# expenasion_board_template.net
KiCad netlist of a schematic drawn in EAGLE
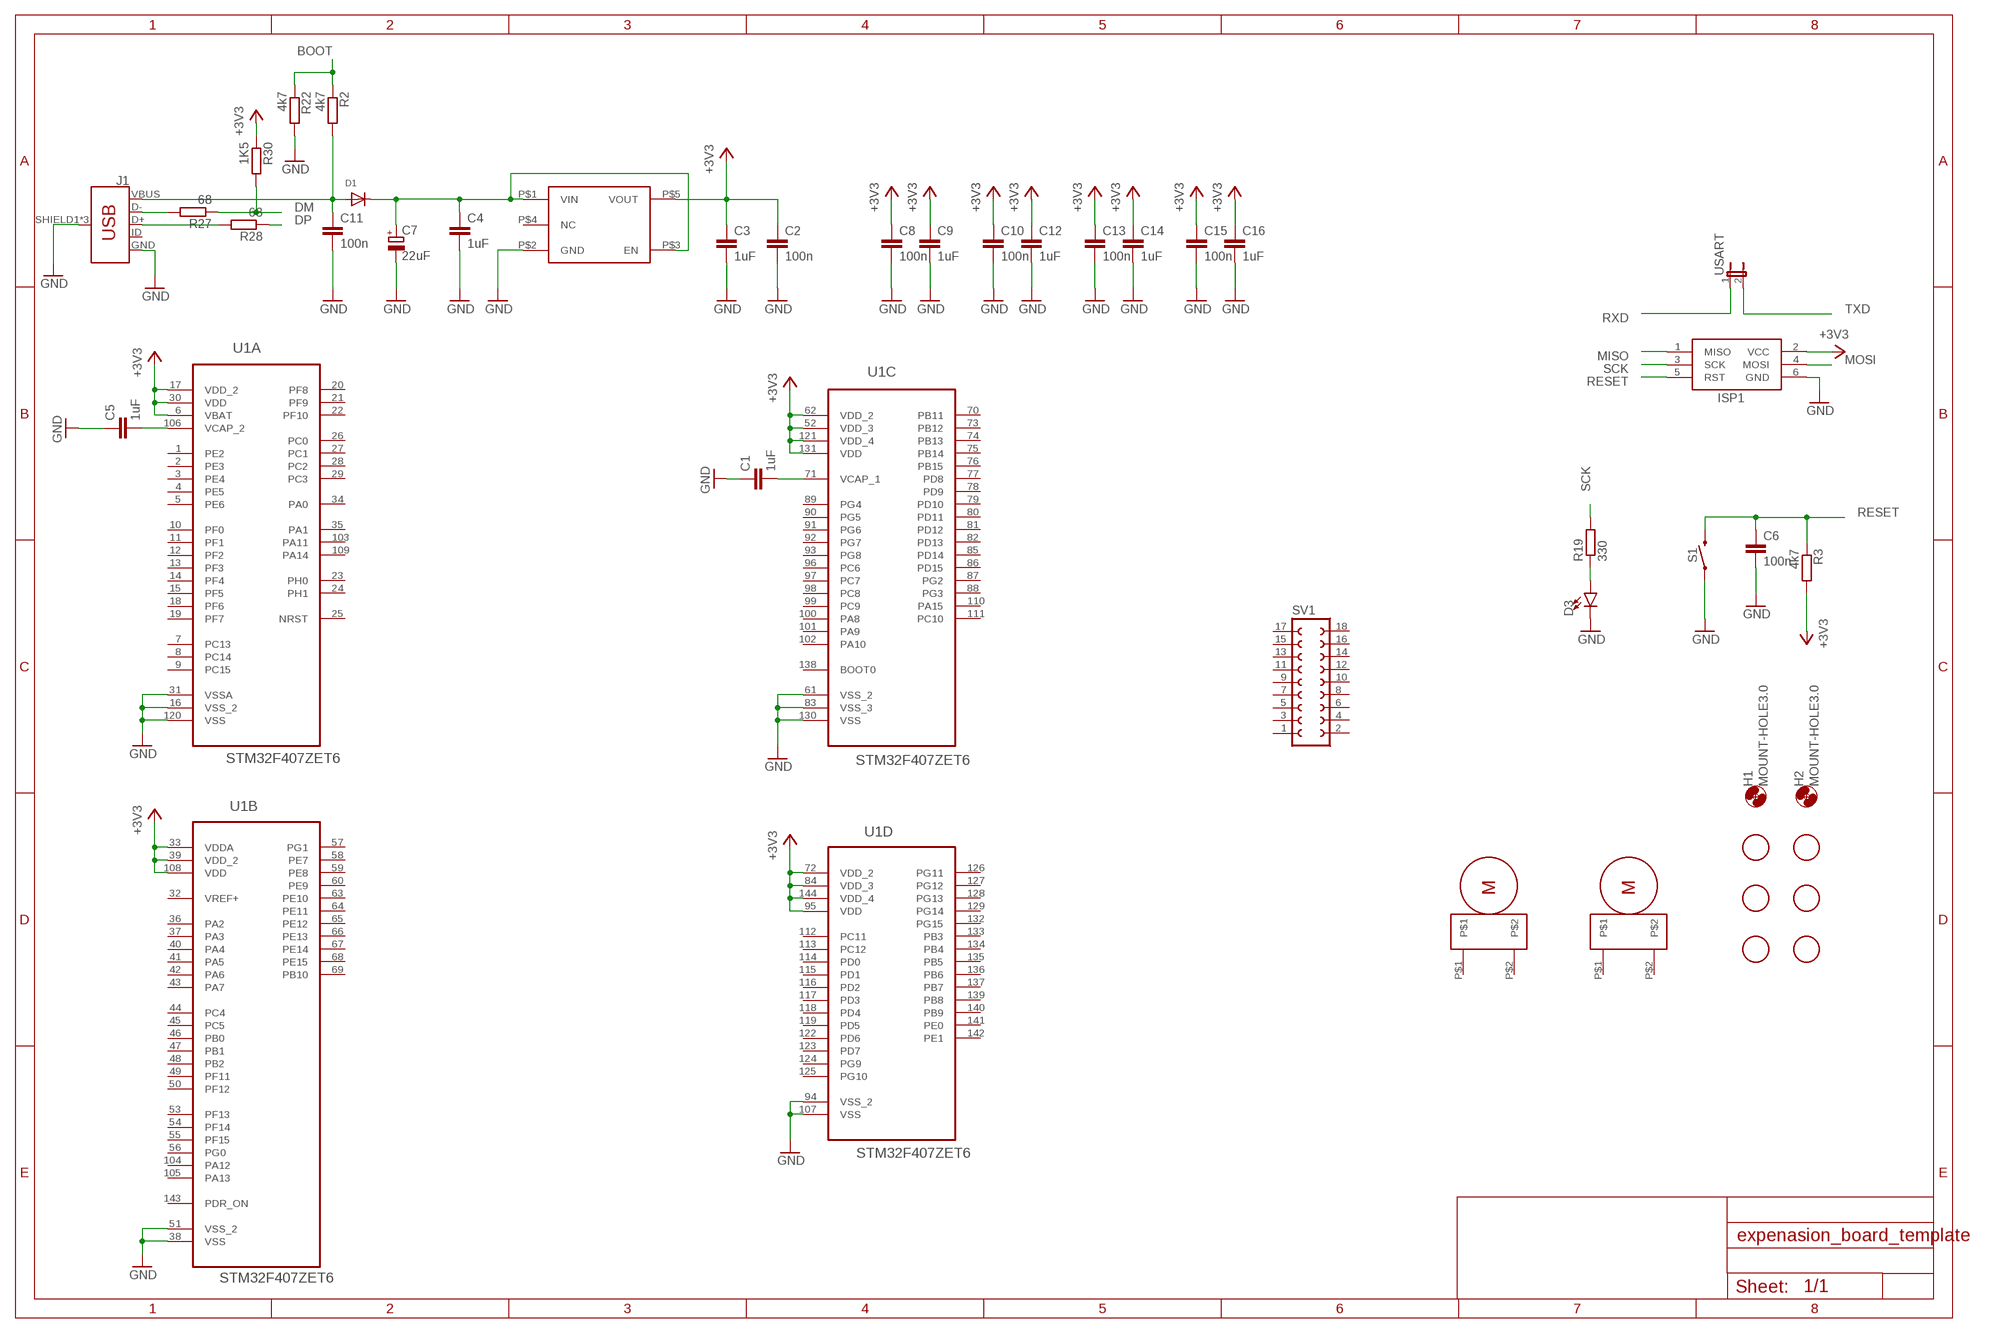
[diagram p0: schematic, sheet 1]

(export (version "E")
  (design (tool "Eeschema 10.0.6"))
  (components
    (comp (ref "C1")
      (value "1uF")
      (footprint "eagle-import:C0805")
      (libsource (lib "eagle-import") (part "C-EUC0805"))
    )
    (comp (ref "C2")
      (value "100n")
      (footprint "eagle-import:C0603")
      (libsource (lib "eagle-import") (part "C-EUC0603"))
    )
    (comp (ref "C3")
      (value "1uF")
      (footprint "eagle-import:C0805")
      (libsource (lib "eagle-import") (part "C-EUC0805"))
    )
    (comp (ref "C4")
      (value "1uF")
      (footprint "eagle-import:C0805")
      (libsource (lib "eagle-import") (part "C-EUC0805"))
    )
    (comp (ref "C5")
      (value "1uF")
      (footprint "eagle-import:C0805")
      (libsource (lib "eagle-import") (part "C-EUC0805"))
    )
    (comp (ref "C6")
      (value "100n")
      (footprint "eagle-import:C0603")
      (libsource (lib "eagle-import") (part "C-EUC0603"))
    )
    (comp (ref "C7")
      (value "22uF")
      (footprint "eagle-import:153CLV-0505")
      (libsource (lib "eagle-import") (part "CPOL-EU153CLV-0505"))
    )
    (comp (ref "C8")
      (value "100n")
      (footprint "eagle-import:C0603")
      (libsource (lib "eagle-import") (part "C-EUC0603"))
    )
    (comp (ref "C9")
      (value "1uF")
      (footprint "eagle-import:C0805")
      (libsource (lib "eagle-import") (part "C-EUC0805"))
    )
    (comp (ref "C10")
      (value "100n")
      (footprint "eagle-import:C0603")
      (libsource (lib "eagle-import") (part "C-EUC0603"))
    )
    (comp (ref "C11")
      (value "100n")
      (footprint "eagle-import:C0603")
      (libsource (lib "eagle-import") (part "C-EUC0603"))
    )
    (comp (ref "C12")
      (value "1uF")
      (footprint "eagle-import:C0805")
      (libsource (lib "eagle-import") (part "C-EUC0805"))
    )
    (comp (ref "C13")
      (value "100n")
      (footprint "eagle-import:C0603")
      (libsource (lib "eagle-import") (part "C-EUC0603"))
    )
    (comp (ref "C14")
      (value "1uF")
      (footprint "eagle-import:C0805")
      (libsource (lib "eagle-import") (part "C-EUC0805"))
    )
    (comp (ref "C15")
      (value "100n")
      (footprint "eagle-import:C0603")
      (libsource (lib "eagle-import") (part "C-EUC0603"))
    )
    (comp (ref "C16")
      (value "1uF")
      (footprint "eagle-import:C0805")
      (libsource (lib "eagle-import") (part "C-EUC0805"))
    )
    (comp (ref "D1")
      (value "DIODE_SOD-123FL")
      (footprint "eagle-import:SOD-123FL")
      (libsource (lib "eagle-import") (part "DIODE_SOD-123FL"))
    )
    (comp (ref "D3")
      (value "LED-FKIT-1206")
      (footprint "eagle-import:FKIT-LED-1206")
      (libsource (lib "eagle-import") (part "LED-FKIT-1206"))
    )
    (comp (ref "H1")
      (value "MOUNT-HOLE3.0")
      (footprint "eagle-import:3,0")
      (libsource (lib "eagle-import") (part "MOUNT-HOLE3.0"))
    )
    (comp (ref "H2")
      (value "MOUNT-HOLE3.0")
      (footprint "eagle-import:3,0")
      (libsource (lib "eagle-import") (part "MOUNT-HOLE3.0"))
    )
    (comp (ref "ISP1")
      (value "AVRISP-6")
      (footprint "eagle-import:AVRISP")
      (libsource (lib "eagle-import") (part "AVRISP-6"))
    )
    (comp (ref "J1")
      (value "USB_MICRO-B_FEMALE-SMT")
      (footprint "eagle-import:USB-B-MICRO-SMD")
      (libsource (lib "eagle-import") (part "USB_MICRO-B_FEMALE-SMT"))
    )
    (comp (ref "R2")
      (value "4k7")
      (footprint "eagle-import:R0603")
      (libsource (lib "eagle-import") (part "R-EU_R0603"))
    )
    (comp (ref "R3")
      (value "4k7")
      (footprint "eagle-import:R0603")
      (libsource (lib "eagle-import") (part "R-EU_R0603"))
    )
    (comp (ref "R19")
      (value "330")
      (footprint "eagle-import:R0603")
      (libsource (lib "eagle-import") (part "R-EU_R0603"))
    )
    (comp (ref "R22")
      (value "4k7")
      (footprint "eagle-import:R0603")
      (libsource (lib "eagle-import") (part "R-EU_R0603"))
    )
    (comp (ref "R27")
      (value "68")
      (footprint "eagle-import:R0603")
      (libsource (lib "eagle-import") (part "R-EU_R0603"))
    )
    (comp (ref "R28")
      (value "68")
      (footprint "eagle-import:R0603")
      (libsource (lib "eagle-import") (part "R-EU_R0603"))
    )
    (comp (ref "R30")
      (value "1K5")
      (footprint "eagle-import:R0603")
      (libsource (lib "eagle-import") (part "R-EU_R0603"))
    )
    (comp (ref "S1")
      (value "MOMENTARY-SWITCH-SPST-SMD-6.2MM-TALL")
      (footprint "eagle-import:TACTILE_SWITCH_SMD_6.2MM_TALL")
      (libsource (lib "eagle-import") (part "MOMENTARY-SWITCH-SPST-SMD-6.2MM-TALL"))
    )
    (comp (ref "SV1")
      (value "FE09-2")
      (footprint "eagle-import:FE09-2")
      (libsource (lib "eagle-import") (part "FE09-2"))
    )
    (comp (ref "U$1")
      (value "FIDUCIAL")
      (footprint "eagle-import:FIDUCIAL_1MM")
      (libsource (lib "eagle-import") (part "FIDUCIAL"))
    )
    (comp (ref "U$2")
      (value "PLANETARY_GEAR_MOTOR")
      (footprint "eagle-import:PLANETARY_GEAR_MOTOR")
      (libsource (lib "eagle-import") (part "PLANETARY_GEAR_MOTOR"))
    )
    (comp (ref "U$3")
      (value "FIDUCIAL")
      (footprint "eagle-import:FIDUCIAL_1MM")
      (libsource (lib "eagle-import") (part "FIDUCIAL"))
    )
    (comp (ref "U$4")
      (value "FIDUCIAL")
      (footprint "eagle-import:FIDUCIAL_1MM")
      (libsource (lib "eagle-import") (part "FIDUCIAL"))
    )
    (comp (ref "U$5")
      (value "FIDUCIAL")
      (footprint "eagle-import:FIDUCIAL_1MM")
      (libsource (lib "eagle-import") (part "FIDUCIAL"))
    )
    (comp (ref "U$6")
      (value "FIDUCIAL")
      (footprint "eagle-import:FIDUCIAL_1MM")
      (libsource (lib "eagle-import") (part "FIDUCIAL"))
    )
    (comp (ref "U$7")
      (value "FIDUCIAL")
      (footprint "eagle-import:FIDUCIAL_1MM")
      (libsource (lib "eagle-import") (part "FIDUCIAL"))
    )
    (comp (ref "U$10")
      (value "PLANETARY_GEAR_MOTOR")
      (footprint "eagle-import:PLANETARY_GEAR_MOTOR")
      (libsource (lib "eagle-import") (part "PLANETARY_GEAR_MOTOR"))
    )
    (comp (ref "U$11")
      (value "MIC5504-3.3Y")
      (footprint "eagle-import:SOT23-5")
      (libsource (lib "eagle-import") (part "MIC5504-3.3Y"))
    )
    (comp (ref "U1")
      (value "STM32F407ZET6")
      (footprint "eagle-import:QFP50P2000X2000X160-144N")
      (libsource (lib "eagle-import") (part "STM32F407ZET6"))
    )
    (comp (ref "USART")
      (value "JP1E")
      (footprint "eagle-import:JP1")
      (libsource (lib "eagle-import") (part "JP1E"))
    )
  )
  (nets
    (net (code "1") (name "+3V3") (class "Default")
      (node (ref "C10") (pin "1") (pinfunction "1_1") (pintype "passive"))
      (node (ref "C12") (pin "1") (pinfunction "1_1") (pintype "passive"))
      (node (ref "C13") (pin "1") (pinfunction "1_1") (pintype "passive"))
      (node (ref "C14") (pin "1") (pinfunction "1_1") (pintype "passive"))
      (node (ref "C15") (pin "1") (pinfunction "1_1") (pintype "passive"))
      (node (ref "C16") (pin "1") (pinfunction "1_1") (pintype "passive"))
      (node (ref "C2") (pin "1") (pinfunction "1_1") (pintype "passive"))
      (node (ref "C3") (pin "1") (pinfunction "1_1") (pintype "passive"))
      (node (ref "C8") (pin "1") (pinfunction "1_1") (pintype "passive"))
      (node (ref "C9") (pin "1") (pinfunction "1_1") (pintype "passive"))
      (node (ref "ISP1") (pin "2") (pinfunction "VCC_2") (pintype "power_in"))
      (node (ref "R3") (pin "2") (pinfunction "2_2") (pintype "passive"))
      (node (ref "R30") (pin "1") (pinfunction "1_1") (pintype "passive"))
      (node (ref "U$11") (pin "P$5") (pinfunction "VOUT_P$5") (pintype "bidirectional"))
      (node (ref "U1") (pin "108") (pinfunction "VDD_108") (pintype "power_in"))
      (node (ref "U1") (pin "121") (pinfunction "VDD_4_121") (pintype "power_in"))
      (node (ref "U1") (pin "131") (pinfunction "VDD_131") (pintype "power_in"))
      (node (ref "U1") (pin "144") (pinfunction "VDD_4_144") (pintype "power_in"))
      (node (ref "U1") (pin "17") (pinfunction "VDD_2_17") (pintype "power_in"))
      (node (ref "U1") (pin "30") (pinfunction "VDD_30") (pintype "power_in"))
      (node (ref "U1") (pin "33") (pinfunction "VDDA_33") (pintype "power_in"))
      (node (ref "U1") (pin "39") (pinfunction "VDD_2_39") (pintype "power_in"))
      (node (ref "U1") (pin "52") (pinfunction "VDD_3_52") (pintype "power_in"))
      (node (ref "U1") (pin "6") (pinfunction "VBAT_6") (pintype "power_in"))
      (node (ref "U1") (pin "62") (pinfunction "VDD_2_62") (pintype "power_in"))
      (node (ref "U1") (pin "72") (pinfunction "VDD_2_72") (pintype "power_in"))
      (node (ref "U1") (pin "84") (pinfunction "VDD_3_84") (pintype "power_in"))
      (node (ref "U1") (pin "95") (pinfunction "VDD_95") (pintype "power_in"))
    )
    (net (code "2") (name "/BOOT") (class "Default")
      (node (ref "R2") (pin "1") (pinfunction "1_1") (pintype "passive"))
      (node (ref "R22") (pin "1") (pinfunction "1_1") (pintype "passive"))
    )
    (net (code "3") (name "/DM") (class "Default")
      (node (ref "R27") (pin "1") (pinfunction "1_1") (pintype "passive"))
      (node (ref "R30") (pin "2") (pinfunction "2_2") (pintype "passive"))
    )
    (net (code "4") (name "/DP") (class "Default")
      (node (ref "R28") (pin "1") (pinfunction "1_1") (pintype "passive"))
    )
    (net (code "5") (name "/MISO") (class "Default")
      (node (ref "ISP1") (pin "1") (pinfunction "MISO_1") (pintype "input"))
    )
    (net (code "6") (name "/MOSI") (class "Default")
      (node (ref "ISP1") (pin "4") (pinfunction "MOSI_4") (pintype "output"))
    )
    (net (code "7") (name "/RESET") (class "Default")
      (node (ref "C6") (pin "1") (pinfunction "1_1") (pintype "passive"))
      (node (ref "ISP1") (pin "5") (pinfunction "RST_5") (pintype "output"))
      (node (ref "R3") (pin "1") (pinfunction "1_1") (pintype "passive"))
      (node (ref "S1") (pin "B2") (pinfunction "2_B2") (pintype "passive"))
    )
    (net (code "8") (name "/RXD") (class "Default")
      (node (ref "USART") (pin "1") (pinfunction "1_1") (pintype "passive"))
    )
    (net (code "9") (name "/SCK") (class "Default")
      (node (ref "ISP1") (pin "3") (pinfunction "SCK_3") (pintype "output"))
      (node (ref "R19") (pin "2") (pinfunction "2_2") (pintype "passive"))
    )
    (net (code "10") (name "/TXD") (class "Default")
      (node (ref "USART") (pin "2") (pinfunction "2_2") (pintype "passive"))
    )
    (net (code "11") (name "/VREF+") (class "Default")
      (node (ref "U1") (pin "32") (pinfunction "VREF+_32") (pintype "power_in"))
    )
    (net (code "12") (name "GND") (class "Default")
      (node (ref "C1") (pin "1") (pinfunction "1_1") (pintype "passive"))
      (node (ref "C10") (pin "2") (pinfunction "2_2") (pintype "passive"))
      (node (ref "C11") (pin "2") (pinfunction "2_2") (pintype "passive"))
      (node (ref "C12") (pin "2") (pinfunction "2_2") (pintype "passive"))
      (node (ref "C13") (pin "2") (pinfunction "2_2") (pintype "passive"))
      (node (ref "C14") (pin "2") (pinfunction "2_2") (pintype "passive"))
      (node (ref "C15") (pin "2") (pinfunction "2_2") (pintype "passive"))
      (node (ref "C16") (pin "2") (pinfunction "2_2") (pintype "passive"))
      (node (ref "C2") (pin "2") (pinfunction "2_2") (pintype "passive"))
      (node (ref "C3") (pin "2") (pinfunction "2_2") (pintype "passive"))
      (node (ref "C4") (pin "2") (pinfunction "2_2") (pintype "passive"))
      (node (ref "C5") (pin "1") (pinfunction "1_1") (pintype "passive"))
      (node (ref "C6") (pin "2") (pinfunction "2_2") (pintype "passive"))
      (node (ref "C7") (pin "-") (pinfunction "-_-") (pintype "passive"))
      (node (ref "C8") (pin "2") (pinfunction "2_2") (pintype "passive"))
      (node (ref "C9") (pin "2") (pinfunction "2_2") (pintype "passive"))
      (node (ref "D3") (pin "C") (pinfunction "C_C") (pintype "passive"))
      (node (ref "ISP1") (pin "6") (pinfunction "GND_6") (pintype "power_in"))
      (node (ref "J1") (pin "GND") (pinfunction "GND_GND") (pintype "power_in"))
      (node (ref "J1") (pin "SHIELD1") (pinfunction "SHIELD_SHIELD1") (pintype "bidirectional"))
      (node (ref "J1") (pin "SHIELD2") (pinfunction "SHIELD_SHIELD2") (pintype "bidirectional"))
      (node (ref "J1") (pin "SHIELD3") (pinfunction "SHIELD_SHIELD3") (pintype "bidirectional"))
      (node (ref "R22") (pin "2") (pinfunction "2_2") (pintype "passive"))
      (node (ref "S1") (pin "A2") (pinfunction "1_A2") (pintype "passive"))
      (node (ref "U$11") (pin "P$2") (pinfunction "GND_P$2") (pintype "bidirectional"))
      (node (ref "U1") (pin "107") (pinfunction "VSS_107") (pintype "passive"))
      (node (ref "U1") (pin "120") (pinfunction "VSS_120") (pintype "passive"))
      (node (ref "U1") (pin "130") (pinfunction "VSS_130") (pintype "passive"))
      (node (ref "U1") (pin "16") (pinfunction "VSS_2_16") (pintype "passive"))
      (node (ref "U1") (pin "31") (pinfunction "VSSA_31") (pintype "passive"))
      (node (ref "U1") (pin "38") (pinfunction "VSS_38") (pintype "passive"))
      (node (ref "U1") (pin "51") (pinfunction "VSS_2_51") (pintype "passive"))
      (node (ref "U1") (pin "61") (pinfunction "VSS_2_61") (pintype "passive"))
      (node (ref "U1") (pin "83") (pinfunction "VSS_3_83") (pintype "passive"))
      (node (ref "U1") (pin "94") (pinfunction "VSS_2_94") (pintype "passive"))
    )
    (net (code "13") (name "Net-(C11-Pad1)") (class "Default")
      (node (ref "C11") (pin "1") (pinfunction "1_1") (pintype "passive"))
      (node (ref "D1") (pin "A") (pinfunction "A_A") (pintype "passive"))
      (node (ref "J1") (pin "VBUS") (pinfunction "VBUS_VBUS") (pintype "power_in"))
      (node (ref "R2") (pin "2") (pinfunction "2_2") (pintype "passive"))
    )
    (net (code "14") (name "Net-(D3-PadA)") (class "Default")
      (node (ref "D3") (pin "A") (pinfunction "A_A") (pintype "passive"))
      (node (ref "R19") (pin "1") (pinfunction "1_1") (pintype "passive"))
    )
    (net (code "15") (name "Net-(J1-PadD+)") (class "Default")
      (node (ref "J1") (pin "D+") (pinfunction "D+_D+") (pintype "bidirectional"))
      (node (ref "R28") (pin "2") (pinfunction "2_2") (pintype "passive"))
    )
    (net (code "16") (name "Net-(J1-PadD-)") (class "Default")
      (node (ref "J1") (pin "D-") (pinfunction "D-_D-") (pintype "bidirectional"))
      (node (ref "R27") (pin "2") (pinfunction "2_2") (pintype "passive"))
    )
    (net (code "17") (name "Net-(U$11-EN)") (class "Default")
      (node (ref "C4") (pin "1") (pinfunction "1_1") (pintype "passive"))
      (node (ref "C7") (pin "+") (pinfunction "+_+") (pintype "passive"))
      (node (ref "D1") (pin "C") (pinfunction "C_C") (pintype "passive"))
      (node (ref "U$11") (pin "P$1") (pinfunction "VIN_P$1") (pintype "bidirectional"))
      (node (ref "U$11") (pin "P$3") (pinfunction "EN_P$3") (pintype "bidirectional"))
    )
    (net (code "18") (name "Net-(U1A-VCAP_2)") (class "Default")
      (node (ref "C5") (pin "2") (pinfunction "2_2") (pintype "passive"))
      (node (ref "U1") (pin "106") (pinfunction "VCAP_2_106") (pintype "power_in"))
    )
    (net (code "19") (name "Net-(U1C-VCAP_1)") (class "Default")
      (node (ref "C1") (pin "2") (pinfunction "2_2") (pintype "passive"))
      (node (ref "U1") (pin "71") (pinfunction "VCAP_1_71") (pintype "power_in"))
    )
    (net (code "20") (name "unconnected-(J1-PadID)") (class "Default")
      (node (ref "J1") (pin "ID") (pinfunction "ID_ID") (pintype "bidirectional"))
    )
    (net (code "21") (name "unconnected-(SV1-Pad1)") (class "Default")
      (node (ref "SV1") (pin "1") (pinfunction "1_1") (pintype "passive"))
    )
    (net (code "22") (name "unconnected-(SV1-Pad2)") (class "Default")
      (node (ref "SV1") (pin "2") (pinfunction "2_2") (pintype "passive"))
    )
    (net (code "23") (name "unconnected-(SV1-Pad3)") (class "Default")
      (node (ref "SV1") (pin "3") (pinfunction "3_3") (pintype "passive"))
    )
    (net (code "24") (name "unconnected-(SV1-Pad4)") (class "Default")
      (node (ref "SV1") (pin "4") (pinfunction "4_4") (pintype "passive"))
    )
    (net (code "25") (name "unconnected-(SV1-Pad5)") (class "Default")
      (node (ref "SV1") (pin "5") (pinfunction "5_5") (pintype "passive"))
    )
    (net (code "26") (name "unconnected-(SV1-Pad6)") (class "Default")
      (node (ref "SV1") (pin "6") (pinfunction "6_6") (pintype "passive"))
    )
    (net (code "27") (name "unconnected-(SV1-Pad7)") (class "Default")
      (node (ref "SV1") (pin "7") (pinfunction "7_7") (pintype "passive"))
    )
    (net (code "28") (name "unconnected-(SV1-Pad8)") (class "Default")
      (node (ref "SV1") (pin "8") (pinfunction "8_8") (pintype "passive"))
    )
    (net (code "29") (name "unconnected-(SV1-Pad9)") (class "Default")
      (node (ref "SV1") (pin "9") (pinfunction "9_9") (pintype "passive"))
    )
    (net (code "30") (name "unconnected-(SV1-Pad10)") (class "Default")
      (node (ref "SV1") (pin "10") (pinfunction "10_10") (pintype "passive"))
    )
    (net (code "31") (name "unconnected-(SV1-Pad11)") (class "Default")
      (node (ref "SV1") (pin "11") (pinfunction "11_11") (pintype "passive"))
    )
    (net (code "32") (name "unconnected-(SV1-Pad12)") (class "Default")
      (node (ref "SV1") (pin "12") (pinfunction "12_12") (pintype "passive"))
    )
    (net (code "33") (name "unconnected-(SV1-Pad13)") (class "Default")
      (node (ref "SV1") (pin "13") (pinfunction "13_13") (pintype "passive"))
    )
    (net (code "34") (name "unconnected-(SV1-Pad14)") (class "Default")
      (node (ref "SV1") (pin "14") (pinfunction "14_14") (pintype "passive"))
    )
    (net (code "35") (name "unconnected-(SV1-Pad15)") (class "Default")
      (node (ref "SV1") (pin "15") (pinfunction "15_15") (pintype "passive"))
    )
    (net (code "36") (name "unconnected-(SV1-Pad16)") (class "Default")
      (node (ref "SV1") (pin "16") (pinfunction "16_16") (pintype "passive"))
    )
    (net (code "37") (name "unconnected-(SV1-Pad17)") (class "Default")
      (node (ref "SV1") (pin "17") (pinfunction "17_17") (pintype "passive"))
    )
    (net (code "38") (name "unconnected-(SV1-Pad18)") (class "Default")
      (node (ref "SV1") (pin "18") (pinfunction "18_18") (pintype "passive"))
    )
    (net (code "39") (name "unconnected-(U$2-PadP$1)") (class "Default")
      (node (ref "U$2") (pin "P$1") (pinfunction "P$1_P$1") (pintype "bidirectional"))
    )
    (net (code "40") (name "unconnected-(U$2-PadP$2)") (class "Default")
      (node (ref "U$2") (pin "P$2") (pinfunction "P$2_P$2") (pintype "bidirectional"))
    )
    (net (code "41") (name "unconnected-(U$10-PadP$1)") (class "Default")
      (node (ref "U$10") (pin "P$1") (pinfunction "P$1_P$1") (pintype "bidirectional"))
    )
    (net (code "42") (name "unconnected-(U$10-PadP$2)") (class "Default")
      (node (ref "U$10") (pin "P$2") (pinfunction "P$2_P$2") (pintype "bidirectional"))
    )
    (net (code "43") (name "unconnected-(U$11-NC-PadP$4)") (class "Default")
      (node (ref "U$11") (pin "P$4") (pinfunction "NC_P$4") (pintype "bidirectional"))
    )
    (net (code "44") (name "unconnected-(U1A-NRST-Pad25)") (class "Default")
      (node (ref "U1") (pin "25") (pinfunction "NRST_25") (pintype "bidirectional"))
    )
    (net (code "45") (name "unconnected-(U1A-PA0-Pad34)") (class "Default")
      (node (ref "U1") (pin "34") (pinfunction "PA0_34") (pintype "bidirectional"))
    )
    (net (code "46") (name "unconnected-(U1A-PA1-Pad35)") (class "Default")
      (node (ref "U1") (pin "35") (pinfunction "PA1_35") (pintype "bidirectional"))
    )
    (net (code "47") (name "unconnected-(U1A-PA11-Pad103)") (class "Default")
      (node (ref "U1") (pin "103") (pinfunction "PA11_103") (pintype "bidirectional"))
    )
    (net (code "48") (name "unconnected-(U1A-PA14-Pad109)") (class "Default")
      (node (ref "U1") (pin "109") (pinfunction "PA14_109") (pintype "bidirectional"))
    )
    (net (code "49") (name "unconnected-(U1A-PC0-Pad26)") (class "Default")
      (node (ref "U1") (pin "26") (pinfunction "PC0_26") (pintype "bidirectional"))
    )
    (net (code "50") (name "unconnected-(U1A-PC1-Pad27)") (class "Default")
      (node (ref "U1") (pin "27") (pinfunction "PC1_27") (pintype "bidirectional"))
    )
    (net (code "51") (name "unconnected-(U1A-PC2-Pad28)") (class "Default")
      (node (ref "U1") (pin "28") (pinfunction "PC2_28") (pintype "bidirectional"))
    )
    (net (code "52") (name "unconnected-(U1A-PC3-Pad29)") (class "Default")
      (node (ref "U1") (pin "29") (pinfunction "PC3_29") (pintype "bidirectional"))
    )
    (net (code "53") (name "unconnected-(U1A-PC13-Pad7)") (class "Default")
      (node (ref "U1") (pin "7") (pinfunction "PC13_7") (pintype "bidirectional"))
    )
    (net (code "54") (name "unconnected-(U1A-PC14-Pad8)") (class "Default")
      (node (ref "U1") (pin "8") (pinfunction "PC14_8") (pintype "bidirectional"))
    )
    (net (code "55") (name "unconnected-(U1A-PC15-Pad9)") (class "Default")
      (node (ref "U1") (pin "9") (pinfunction "PC15_9") (pintype "bidirectional"))
    )
    (net (code "56") (name "unconnected-(U1A-PE2-Pad1)") (class "Default")
      (node (ref "U1") (pin "1") (pinfunction "PE2_1") (pintype "bidirectional"))
    )
    (net (code "57") (name "unconnected-(U1A-PE3-Pad2)") (class "Default")
      (node (ref "U1") (pin "2") (pinfunction "PE3_2") (pintype "bidirectional"))
    )
    (net (code "58") (name "unconnected-(U1A-PE4-Pad3)") (class "Default")
      (node (ref "U1") (pin "3") (pinfunction "PE4_3") (pintype "bidirectional"))
    )
    (net (code "59") (name "unconnected-(U1A-PE5-Pad4)") (class "Default")
      (node (ref "U1") (pin "4") (pinfunction "PE5_4") (pintype "bidirectional"))
    )
    (net (code "60") (name "unconnected-(U1A-PE6-Pad5)") (class "Default")
      (node (ref "U1") (pin "5") (pinfunction "PE6_5") (pintype "bidirectional"))
    )
    (net (code "61") (name "unconnected-(U1A-PF0-Pad10)") (class "Default")
      (node (ref "U1") (pin "10") (pinfunction "PF0_10") (pintype "bidirectional"))
    )
    (net (code "62") (name "unconnected-(U1A-PF1-Pad11)") (class "Default")
      (node (ref "U1") (pin "11") (pinfunction "PF1_11") (pintype "bidirectional"))
    )
    (net (code "63") (name "unconnected-(U1A-PF2-Pad12)") (class "Default")
      (node (ref "U1") (pin "12") (pinfunction "PF2_12") (pintype "bidirectional"))
    )
    (net (code "64") (name "unconnected-(U1A-PF3-Pad13)") (class "Default")
      (node (ref "U1") (pin "13") (pinfunction "PF3_13") (pintype "bidirectional"))
    )
    (net (code "65") (name "unconnected-(U1A-PF4-Pad14)") (class "Default")
      (node (ref "U1") (pin "14") (pinfunction "PF4_14") (pintype "bidirectional"))
    )
    (net (code "66") (name "unconnected-(U1A-PF5-Pad15)") (class "Default")
      (node (ref "U1") (pin "15") (pinfunction "PF5_15") (pintype "bidirectional"))
    )
    (net (code "67") (name "unconnected-(U1A-PF6-Pad18)") (class "Default")
      (node (ref "U1") (pin "18") (pinfunction "PF6_18") (pintype "bidirectional"))
    )
    (net (code "68") (name "unconnected-(U1A-PF7-Pad19)") (class "Default")
      (node (ref "U1") (pin "19") (pinfunction "PF7_19") (pintype "bidirectional"))
    )
    (net (code "69") (name "unconnected-(U1A-PF8-Pad20)") (class "Default")
      (node (ref "U1") (pin "20") (pinfunction "PF8_20") (pintype "bidirectional"))
    )
    (net (code "70") (name "unconnected-(U1A-PF9-Pad21)") (class "Default")
      (node (ref "U1") (pin "21") (pinfunction "PF9_21") (pintype "bidirectional"))
    )
    (net (code "71") (name "unconnected-(U1A-PF10-Pad22)") (class "Default")
      (node (ref "U1") (pin "22") (pinfunction "PF10_22") (pintype "bidirectional"))
    )
    (net (code "72") (name "unconnected-(U1A-PH0-Pad23)") (class "Default")
      (node (ref "U1") (pin "23") (pinfunction "PH0_23") (pintype "bidirectional"))
    )
    (net (code "73") (name "unconnected-(U1A-PH1-Pad24)") (class "Default")
      (node (ref "U1") (pin "24") (pinfunction "PH1_24") (pintype "bidirectional"))
    )
    (net (code "74") (name "unconnected-(U1B-PA2-Pad36)") (class "Default")
      (node (ref "U1") (pin "36") (pinfunction "PA2_36") (pintype "bidirectional"))
    )
    (net (code "75") (name "unconnected-(U1B-PA3-Pad37)") (class "Default")
      (node (ref "U1") (pin "37") (pinfunction "PA3_37") (pintype "bidirectional"))
    )
    (net (code "76") (name "unconnected-(U1B-PA4-Pad40)") (class "Default")
      (node (ref "U1") (pin "40") (pinfunction "PA4_40") (pintype "bidirectional"))
    )
    (net (code "77") (name "unconnected-(U1B-PA5-Pad41)") (class "Default")
      (node (ref "U1") (pin "41") (pinfunction "PA5_41") (pintype "bidirectional"))
    )
    (net (code "78") (name "unconnected-(U1B-PA6-Pad42)") (class "Default")
      (node (ref "U1") (pin "42") (pinfunction "PA6_42") (pintype "bidirectional"))
    )
    (net (code "79") (name "unconnected-(U1B-PA7-Pad43)") (class "Default")
      (node (ref "U1") (pin "43") (pinfunction "PA7_43") (pintype "bidirectional"))
    )
    (net (code "80") (name "unconnected-(U1B-PA12-Pad104)") (class "Default")
      (node (ref "U1") (pin "104") (pinfunction "PA12_104") (pintype "bidirectional"))
    )
    (net (code "81") (name "unconnected-(U1B-PA13-Pad105)") (class "Default")
      (node (ref "U1") (pin "105") (pinfunction "PA13_105") (pintype "bidirectional"))
    )
    (net (code "82") (name "unconnected-(U1B-PB0-Pad46)") (class "Default")
      (node (ref "U1") (pin "46") (pinfunction "PB0_46") (pintype "bidirectional"))
    )
    (net (code "83") (name "unconnected-(U1B-PB1-Pad47)") (class "Default")
      (node (ref "U1") (pin "47") (pinfunction "PB1_47") (pintype "bidirectional"))
    )
    (net (code "84") (name "unconnected-(U1B-PB2-Pad48)") (class "Default")
      (node (ref "U1") (pin "48") (pinfunction "PB2_48") (pintype "bidirectional"))
    )
    (net (code "85") (name "unconnected-(U1B-PB10-Pad69)") (class "Default")
      (node (ref "U1") (pin "69") (pinfunction "PB10_69") (pintype "bidirectional"))
    )
    (net (code "86") (name "unconnected-(U1B-PC4-Pad44)") (class "Default")
      (node (ref "U1") (pin "44") (pinfunction "PC4_44") (pintype "bidirectional"))
    )
    (net (code "87") (name "unconnected-(U1B-PC5-Pad45)") (class "Default")
      (node (ref "U1") (pin "45") (pinfunction "PC5_45") (pintype "bidirectional"))
    )
    (net (code "88") (name "unconnected-(U1B-PDR_ON-Pad143)") (class "Default")
      (node (ref "U1") (pin "143") (pinfunction "PDR_ON_143") (pintype "bidirectional"))
    )
    (net (code "89") (name "unconnected-(U1B-PE7-Pad58)") (class "Default")
      (node (ref "U1") (pin "58") (pinfunction "PE7_58") (pintype "bidirectional"))
    )
    (net (code "90") (name "unconnected-(U1B-PE8-Pad59)") (class "Default")
      (node (ref "U1") (pin "59") (pinfunction "PE8_59") (pintype "bidirectional"))
    )
    (net (code "91") (name "unconnected-(U1B-PE9-Pad60)") (class "Default")
      (node (ref "U1") (pin "60") (pinfunction "PE9_60") (pintype "bidirectional"))
    )
    (net (code "92") (name "unconnected-(U1B-PE10-Pad63)") (class "Default")
      (node (ref "U1") (pin "63") (pinfunction "PE10_63") (pintype "bidirectional"))
    )
    (net (code "93") (name "unconnected-(U1B-PE11-Pad64)") (class "Default")
      (node (ref "U1") (pin "64") (pinfunction "PE11_64") (pintype "bidirectional"))
    )
    (net (code "94") (name "unconnected-(U1B-PE12-Pad65)") (class "Default")
      (node (ref "U1") (pin "65") (pinfunction "PE12_65") (pintype "bidirectional"))
    )
    (net (code "95") (name "unconnected-(U1B-PE13-Pad66)") (class "Default")
      (node (ref "U1") (pin "66") (pinfunction "PE13_66") (pintype "bidirectional"))
    )
    (net (code "96") (name "unconnected-(U1B-PE14-Pad67)") (class "Default")
      (node (ref "U1") (pin "67") (pinfunction "PE14_67") (pintype "bidirectional"))
    )
    (net (code "97") (name "unconnected-(U1B-PE15-Pad68)") (class "Default")
      (node (ref "U1") (pin "68") (pinfunction "PE15_68") (pintype "bidirectional"))
    )
    (net (code "98") (name "unconnected-(U1B-PF11-Pad49)") (class "Default")
      (node (ref "U1") (pin "49") (pinfunction "PF11_49") (pintype "bidirectional"))
    )
    (net (code "99") (name "unconnected-(U1B-PF12-Pad50)") (class "Default")
      (node (ref "U1") (pin "50") (pinfunction "PF12_50") (pintype "bidirectional"))
    )
    (net (code "100") (name "unconnected-(U1B-PF13-Pad53)") (class "Default")
      (node (ref "U1") (pin "53") (pinfunction "PF13_53") (pintype "bidirectional"))
    )
    (net (code "101") (name "unconnected-(U1B-PF14-Pad54)") (class "Default")
      (node (ref "U1") (pin "54") (pinfunction "PF14_54") (pintype "bidirectional"))
    )
    (net (code "102") (name "unconnected-(U1B-PF15-Pad55)") (class "Default")
      (node (ref "U1") (pin "55") (pinfunction "PF15_55") (pintype "bidirectional"))
    )
    (net (code "103") (name "unconnected-(U1B-PG0-Pad56)") (class "Default")
      (node (ref "U1") (pin "56") (pinfunction "PG0_56") (pintype "bidirectional"))
    )
    (net (code "104") (name "unconnected-(U1B-PG1-Pad57)") (class "Default")
      (node (ref "U1") (pin "57") (pinfunction "PG1_57") (pintype "bidirectional"))
    )
    (net (code "105") (name "unconnected-(U1C-BOOT0-Pad138)") (class "Default")
      (node (ref "U1") (pin "138") (pinfunction "BOOT0_138") (pintype "input"))
    )
    (net (code "106") (name "unconnected-(U1C-PA8-Pad100)") (class "Default")
      (node (ref "U1") (pin "100") (pinfunction "PA8_100") (pintype "bidirectional"))
    )
    (net (code "107") (name "unconnected-(U1C-PA9-Pad101)") (class "Default")
      (node (ref "U1") (pin "101") (pinfunction "PA9_101") (pintype "bidirectional"))
    )
    (net (code "108") (name "unconnected-(U1C-PA10-Pad102)") (class "Default")
      (node (ref "U1") (pin "102") (pinfunction "PA10_102") (pintype "bidirectional"))
    )
    (net (code "109") (name "unconnected-(U1C-PA15-Pad110)") (class "Default")
      (node (ref "U1") (pin "110") (pinfunction "PA15_110") (pintype "bidirectional"))
    )
    (net (code "110") (name "unconnected-(U1C-PB11-Pad70)") (class "Default")
      (node (ref "U1") (pin "70") (pinfunction "PB11_70") (pintype "bidirectional"))
    )
    (net (code "111") (name "unconnected-(U1C-PB12-Pad73)") (class "Default")
      (node (ref "U1") (pin "73") (pinfunction "PB12_73") (pintype "bidirectional"))
    )
    (net (code "112") (name "unconnected-(U1C-PB13-Pad74)") (class "Default")
      (node (ref "U1") (pin "74") (pinfunction "PB13_74") (pintype "bidirectional"))
    )
    (net (code "113") (name "unconnected-(U1C-PB14-Pad75)") (class "Default")
      (node (ref "U1") (pin "75") (pinfunction "PB14_75") (pintype "bidirectional"))
    )
    (net (code "114") (name "unconnected-(U1C-PB15-Pad76)") (class "Default")
      (node (ref "U1") (pin "76") (pinfunction "PB15_76") (pintype "bidirectional"))
    )
    (net (code "115") (name "unconnected-(U1C-PC6-Pad96)") (class "Default")
      (node (ref "U1") (pin "96") (pinfunction "PC6_96") (pintype "bidirectional"))
    )
    (net (code "116") (name "unconnected-(U1C-PC7-Pad97)") (class "Default")
      (node (ref "U1") (pin "97") (pinfunction "PC7_97") (pintype "bidirectional"))
    )
    (net (code "117") (name "unconnected-(U1C-PC8-Pad98)") (class "Default")
      (node (ref "U1") (pin "98") (pinfunction "PC8_98") (pintype "bidirectional"))
    )
    (net (code "118") (name "unconnected-(U1C-PC9-Pad99)") (class "Default")
      (node (ref "U1") (pin "99") (pinfunction "PC9_99") (pintype "bidirectional"))
    )
    (net (code "119") (name "unconnected-(U1C-PC10-Pad111)") (class "Default")
      (node (ref "U1") (pin "111") (pinfunction "PC10_111") (pintype "bidirectional"))
    )
    (net (code "120") (name "unconnected-(U1C-PD8-Pad77)") (class "Default")
      (node (ref "U1") (pin "77") (pinfunction "PD8_77") (pintype "bidirectional"))
    )
    (net (code "121") (name "unconnected-(U1C-PD9-Pad78)") (class "Default")
      (node (ref "U1") (pin "78") (pinfunction "PD9_78") (pintype "bidirectional"))
    )
    (net (code "122") (name "unconnected-(U1C-PD10-Pad79)") (class "Default")
      (node (ref "U1") (pin "79") (pinfunction "PD10_79") (pintype "bidirectional"))
    )
    (net (code "123") (name "unconnected-(U1C-PD11-Pad80)") (class "Default")
      (node (ref "U1") (pin "80") (pinfunction "PD11_80") (pintype "bidirectional"))
    )
    (net (code "124") (name "unconnected-(U1C-PD12-Pad81)") (class "Default")
      (node (ref "U1") (pin "81") (pinfunction "PD12_81") (pintype "bidirectional"))
    )
    (net (code "125") (name "unconnected-(U1C-PD13-Pad82)") (class "Default")
      (node (ref "U1") (pin "82") (pinfunction "PD13_82") (pintype "bidirectional"))
    )
    (net (code "126") (name "unconnected-(U1C-PD14-Pad85)") (class "Default")
      (node (ref "U1") (pin "85") (pinfunction "PD14_85") (pintype "bidirectional"))
    )
    (net (code "127") (name "unconnected-(U1C-PD15-Pad86)") (class "Default")
      (node (ref "U1") (pin "86") (pinfunction "PD15_86") (pintype "bidirectional"))
    )
    (net (code "128") (name "unconnected-(U1C-PG2-Pad87)") (class "Default")
      (node (ref "U1") (pin "87") (pinfunction "PG2_87") (pintype "bidirectional"))
    )
    (net (code "129") (name "unconnected-(U1C-PG3-Pad88)") (class "Default")
      (node (ref "U1") (pin "88") (pinfunction "PG3_88") (pintype "bidirectional"))
    )
    (net (code "130") (name "unconnected-(U1C-PG4-Pad89)") (class "Default")
      (node (ref "U1") (pin "89") (pinfunction "PG4_89") (pintype "bidirectional"))
    )
    (net (code "131") (name "unconnected-(U1C-PG5-Pad90)") (class "Default")
      (node (ref "U1") (pin "90") (pinfunction "PG5_90") (pintype "bidirectional"))
    )
    (net (code "132") (name "unconnected-(U1C-PG6-Pad91)") (class "Default")
      (node (ref "U1") (pin "91") (pinfunction "PG6_91") (pintype "bidirectional"))
    )
    (net (code "133") (name "unconnected-(U1C-PG7-Pad92)") (class "Default")
      (node (ref "U1") (pin "92") (pinfunction "PG7_92") (pintype "bidirectional"))
    )
    (net (code "134") (name "unconnected-(U1C-PG8-Pad93)") (class "Default")
      (node (ref "U1") (pin "93") (pinfunction "PG8_93") (pintype "bidirectional"))
    )
    (net (code "135") (name "unconnected-(U1D-PB3-Pad133)") (class "Default")
      (node (ref "U1") (pin "133") (pinfunction "PB3_133") (pintype "bidirectional"))
    )
    (net (code "136") (name "unconnected-(U1D-PB4-Pad134)") (class "Default")
      (node (ref "U1") (pin "134") (pinfunction "PB4_134") (pintype "bidirectional"))
    )
    (net (code "137") (name "unconnected-(U1D-PB5-Pad135)") (class "Default")
      (node (ref "U1") (pin "135") (pinfunction "PB5_135") (pintype "bidirectional"))
    )
    (net (code "138") (name "unconnected-(U1D-PB6-Pad136)") (class "Default")
      (node (ref "U1") (pin "136") (pinfunction "PB6_136") (pintype "bidirectional"))
    )
    (net (code "139") (name "unconnected-(U1D-PB7-Pad137)") (class "Default")
      (node (ref "U1") (pin "137") (pinfunction "PB7_137") (pintype "bidirectional"))
    )
    (net (code "140") (name "unconnected-(U1D-PB8-Pad139)") (class "Default")
      (node (ref "U1") (pin "139") (pinfunction "PB8_139") (pintype "bidirectional"))
    )
    (net (code "141") (name "unconnected-(U1D-PB9-Pad140)") (class "Default")
      (node (ref "U1") (pin "140") (pinfunction "PB9_140") (pintype "bidirectional"))
    )
    (net (code "142") (name "unconnected-(U1D-PC11-Pad112)") (class "Default")
      (node (ref "U1") (pin "112") (pinfunction "PC11_112") (pintype "bidirectional"))
    )
    (net (code "143") (name "unconnected-(U1D-PC12-Pad113)") (class "Default")
      (node (ref "U1") (pin "113") (pinfunction "PC12_113") (pintype "bidirectional"))
    )
    (net (code "144") (name "unconnected-(U1D-PD0-Pad114)") (class "Default")
      (node (ref "U1") (pin "114") (pinfunction "PD0_114") (pintype "bidirectional"))
    )
    (net (code "145") (name "unconnected-(U1D-PD1-Pad115)") (class "Default")
      (node (ref "U1") (pin "115") (pinfunction "PD1_115") (pintype "bidirectional"))
    )
    (net (code "146") (name "unconnected-(U1D-PD2-Pad116)") (class "Default")
      (node (ref "U1") (pin "116") (pinfunction "PD2_116") (pintype "bidirectional"))
    )
    (net (code "147") (name "unconnected-(U1D-PD3-Pad117)") (class "Default")
      (node (ref "U1") (pin "117") (pinfunction "PD3_117") (pintype "bidirectional"))
    )
    (net (code "148") (name "unconnected-(U1D-PD4-Pad118)") (class "Default")
      (node (ref "U1") (pin "118") (pinfunction "PD4_118") (pintype "bidirectional"))
    )
    (net (code "149") (name "unconnected-(U1D-PD5-Pad119)") (class "Default")
      (node (ref "U1") (pin "119") (pinfunction "PD5_119") (pintype "bidirectional"))
    )
    (net (code "150") (name "unconnected-(U1D-PD6-Pad122)") (class "Default")
      (node (ref "U1") (pin "122") (pinfunction "PD6_122") (pintype "bidirectional"))
    )
    (net (code "151") (name "unconnected-(U1D-PD7-Pad123)") (class "Default")
      (node (ref "U1") (pin "123") (pinfunction "PD7_123") (pintype "bidirectional"))
    )
    (net (code "152") (name "unconnected-(U1D-PE0-Pad141)") (class "Default")
      (node (ref "U1") (pin "141") (pinfunction "PE0_141") (pintype "bidirectional"))
    )
    (net (code "153") (name "unconnected-(U1D-PE1-Pad142)") (class "Default")
      (node (ref "U1") (pin "142") (pinfunction "PE1_142") (pintype "bidirectional"))
    )
    (net (code "154") (name "unconnected-(U1D-PG9-Pad124)") (class "Default")
      (node (ref "U1") (pin "124") (pinfunction "PG9_124") (pintype "bidirectional"))
    )
    (net (code "155") (name "unconnected-(U1D-PG10-Pad125)") (class "Default")
      (node (ref "U1") (pin "125") (pinfunction "PG10_125") (pintype "bidirectional"))
    )
    (net (code "156") (name "unconnected-(U1D-PG11-Pad126)") (class "Default")
      (node (ref "U1") (pin "126") (pinfunction "PG11_126") (pintype "bidirectional"))
    )
    (net (code "157") (name "unconnected-(U1D-PG12-Pad127)") (class "Default")
      (node (ref "U1") (pin "127") (pinfunction "PG12_127") (pintype "bidirectional"))
    )
    (net (code "158") (name "unconnected-(U1D-PG13-Pad128)") (class "Default")
      (node (ref "U1") (pin "128") (pinfunction "PG13_128") (pintype "bidirectional"))
    )
    (net (code "159") (name "unconnected-(U1D-PG14-Pad129)") (class "Default")
      (node (ref "U1") (pin "129") (pinfunction "PG14_129") (pintype "bidirectional"))
    )
    (net (code "160") (name "unconnected-(U1D-PG15-Pad132)") (class "Default")
      (node (ref "U1") (pin "132") (pinfunction "PG15_132") (pintype "bidirectional"))
    )
  )
)
